# 0125-humidity-temp-sensor.net
KiCad netlist of a schematic drawn in EAGLE
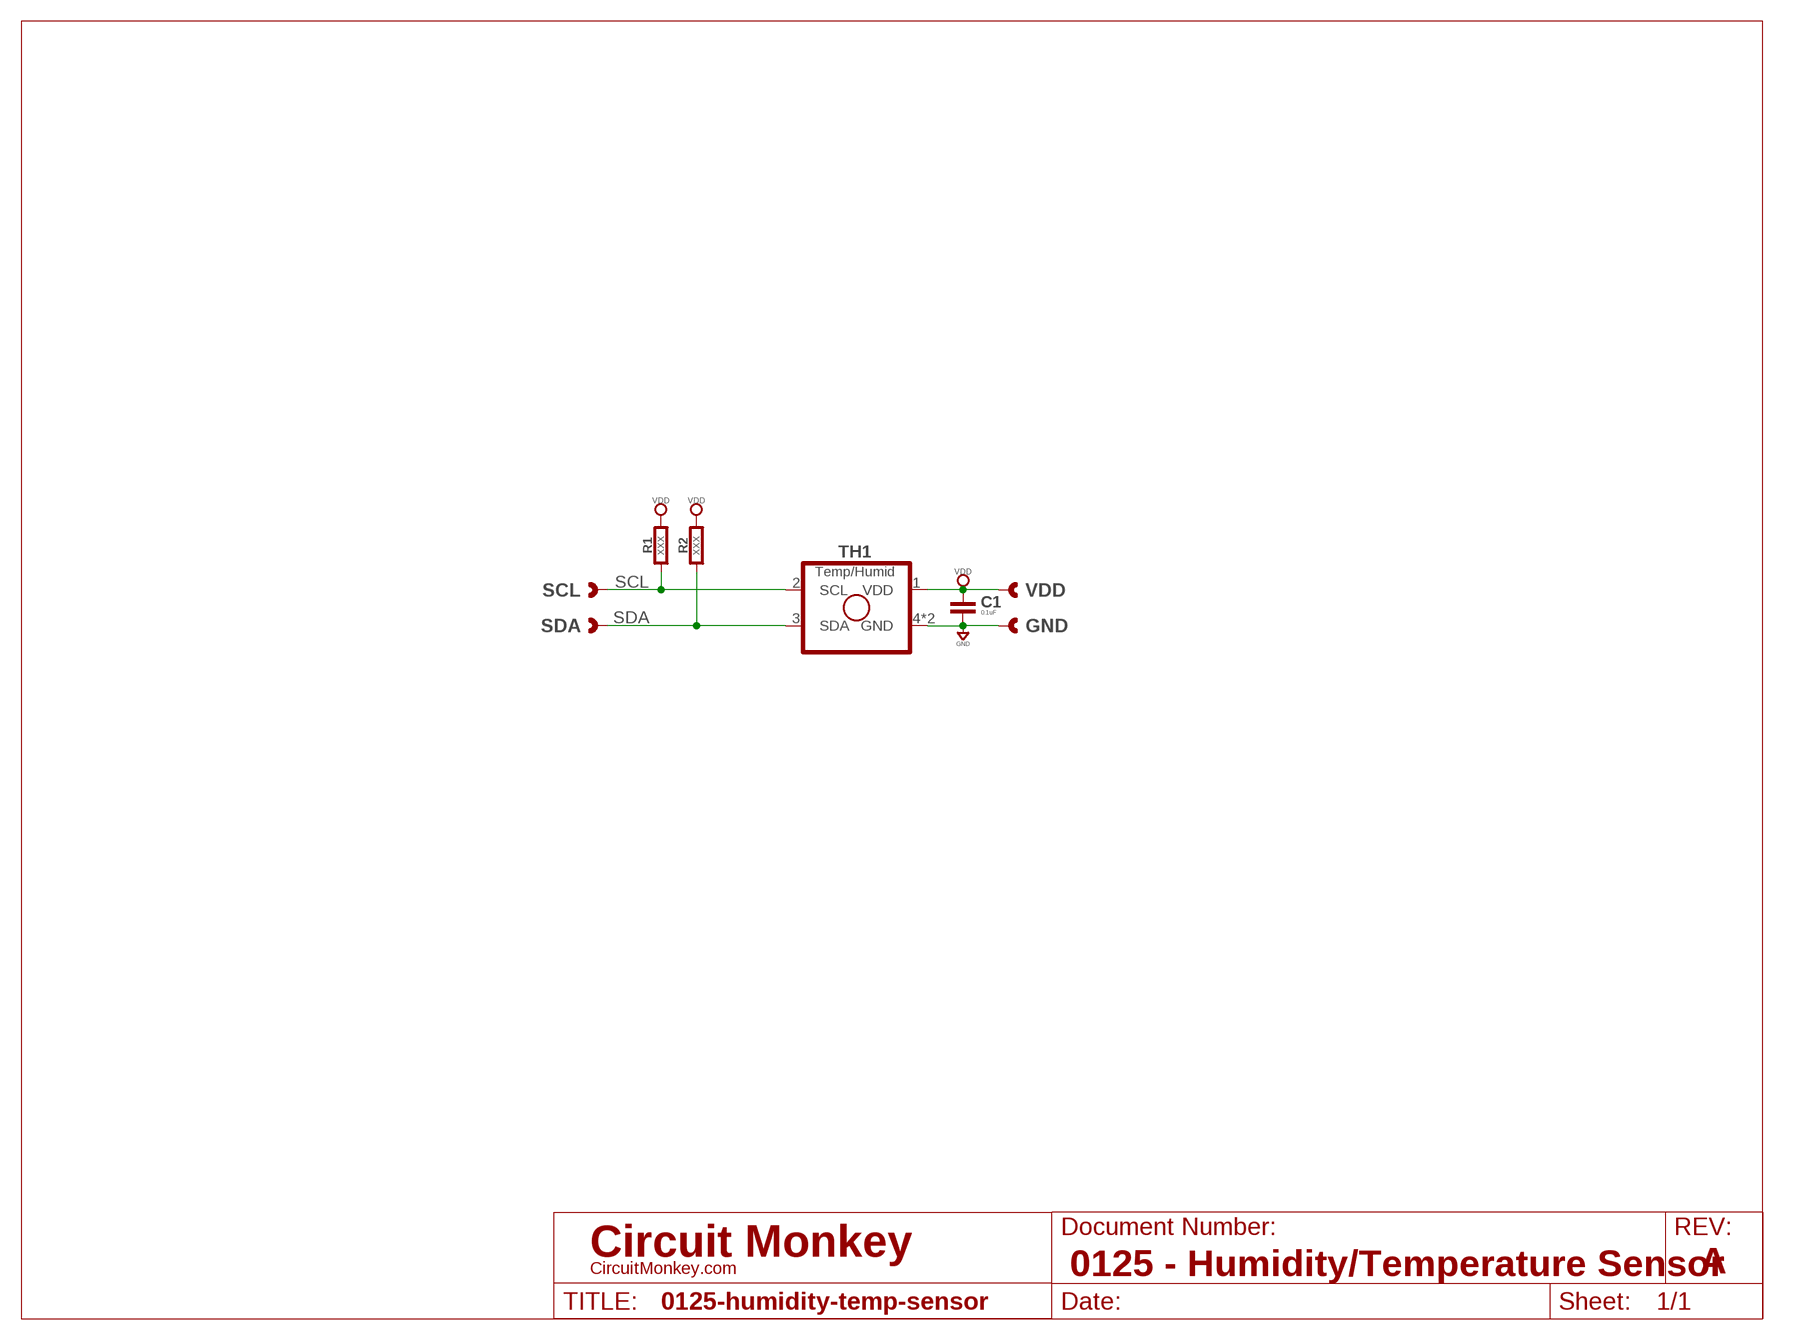
[diagram p0: schematic, sheet 1]

(export (version "E")
  (design (tool "Eeschema 10.0.6"))
  (components
    (comp (ref "C1")
      (value "0.1uF")
      (footprint "eagle-import:0402-CAP")
      (libsource (lib "eagle-import") (part "CAPACITOR0402"))
    )
    (comp (ref "GND")
      (value "CAST-01X12.00MM")
      (footprint "eagle-import:CAST01-2.00MM")
      (libsource (lib "eagle-import") (part "CAST-01X12.00MM"))
    )
    (comp (ref "R1")
      (value "XXX")
      (footprint "eagle-import:0402-RES")
      (libsource (lib "eagle-import") (part "RESISTOR0402"))
    )
    (comp (ref "R2")
      (value "XXX")
      (footprint "eagle-import:0402-RES")
      (libsource (lib "eagle-import") (part "RESISTOR0402"))
    )
    (comp (ref "SCL")
      (value "CAST-01X12.00MM")
      (footprint "eagle-import:CAST01-2.00MM")
      (libsource (lib "eagle-import") (part "CAST-01X12.00MM"))
    )
    (comp (ref "SDA")
      (value "CAST-01X12.00MM")
      (footprint "eagle-import:CAST01-2.00MM")
      (libsource (lib "eagle-import") (part "CAST-01X12.00MM"))
    )
    (comp (ref "TH1")
      (value "Temp/Humid")
      (footprint "eagle-import:SHTC3")
      (fields (field (name "MFR") "Sensiron") (field (name "MPN") "SHTC3"))
      (libsource (lib "eagle-import") (part "I2C-SHTC3"))
    )
    (comp (ref "VDD")
      (value "CAST-01X12.00MM")
      (footprint "eagle-import:CAST01-2.00MM")
      (libsource (lib "eagle-import") (part "CAST-01X12.00MM"))
    )
  )
  (nets
    (net (code "1") (name "/SCL") (class "Default")
      (node (ref "R1") (pin "1") (pinfunction "1_1") (pintype "passive"))
      (node (ref "SCL") (pin "1") (pinfunction "1_1") (pintype "bidirectional"))
      (node (ref "SCL") (pin "P$1") (pinfunction "1_P$1") (pintype "bidirectional"))
      (node (ref "SCL") (pin "P$2") (pinfunction "1_P$2") (pintype "bidirectional"))
      (node (ref "TH1") (pin "2") (pinfunction "SCL_2") (pintype "bidirectional"))
    )
    (net (code "2") (name "/SDA") (class "Default")
      (node (ref "R2") (pin "1") (pinfunction "1_1") (pintype "passive"))
      (node (ref "SDA") (pin "1") (pinfunction "1_1") (pintype "bidirectional"))
      (node (ref "SDA") (pin "P$1") (pinfunction "1_P$1") (pintype "bidirectional"))
      (node (ref "SDA") (pin "P$2") (pinfunction "1_P$2") (pintype "bidirectional"))
      (node (ref "TH1") (pin "3") (pinfunction "SDA_3") (pintype "bidirectional"))
    )
    (net (code "3") (name "GND") (class "Default")
      (node (ref "C1") (pin "2") (pinfunction "2_2") (pintype "passive"))
      (node (ref "GND") (pin "1") (pinfunction "1_1") (pintype "bidirectional"))
      (node (ref "GND") (pin "P$1") (pinfunction "1_P$1") (pintype "bidirectional"))
      (node (ref "GND") (pin "P$2") (pinfunction "1_P$2") (pintype "bidirectional"))
      (node (ref "TH1") (pin "4") (pinfunction "GND_4") (pintype "bidirectional"))
      (node (ref "TH1") (pin "PAD") (pinfunction "GND_PAD") (pintype "bidirectional"))
    )
    (net (code "4") (name "VDD") (class "Default")
      (node (ref "C1") (pin "1") (pinfunction "1_1") (pintype "passive"))
      (node (ref "R1") (pin "2") (pinfunction "2_2") (pintype "passive"))
      (node (ref "R2") (pin "2") (pinfunction "2_2") (pintype "passive"))
      (node (ref "TH1") (pin "1") (pinfunction "VDD_1") (pintype "bidirectional"))
      (node (ref "VDD") (pin "1") (pinfunction "1_1") (pintype "bidirectional"))
      (node (ref "VDD") (pin "P$1") (pinfunction "1_P$1") (pintype "bidirectional"))
      (node (ref "VDD") (pin "P$2") (pinfunction "1_P$2") (pintype "bidirectional"))
    )
  )
)
